# Power_Management.net
KiCad netlist of a schematic drawn in Altium Designer
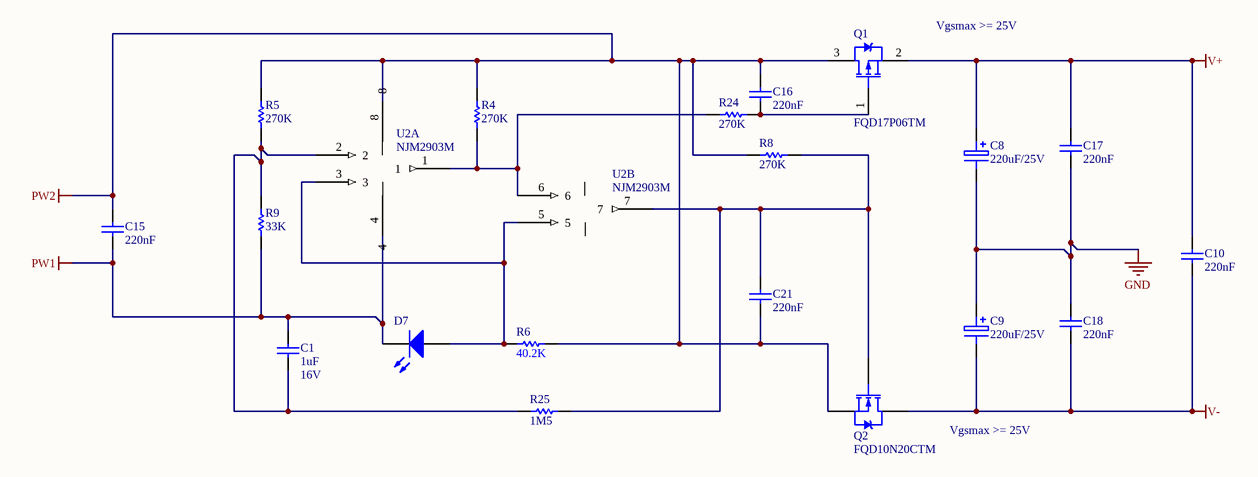
[diagram p0: Power Management.SchDoc]

(export (version "E")
  (design (tool "Eeschema 10.0.6"))
  (components
    (comp (ref "C1")
      (value "1uF")
      (footprint "CAPC1608L")
      (description "CAP CER 1uF Y5V -20% +80% 16V 0603")
      (fields (field (name "MAX VOLTAGE") "16V"))
      (libsource (lib "ECE Components_16_2") (part "CC_1uF_0603"))
    )
    (comp (ref "C8")
      (value "220uF/25V")
      (footprint "UUQ1E221MCL1GS")
      (description "220µF 25V Aluminum Capacitors Radial, Can - SMD 1000 Hrs @ 105°C")
      (fields (field (name "MANUFACTURER") "Nichcon"))
      (libsource (lib "ECE Components_16_2") (part "CA_100uF_16V"))
    )
    (comp (ref "C9")
      (value "220uF/25V")
      (footprint "UUQ1E221MCL1GS")
      (description "220µF 25V Aluminum Capacitors Radial, Can - SMD 1000 Hrs @ 105°C")
      (fields (field (name "MANUFACTURER") "Nichcon"))
      (libsource (lib "ECE Components_16_2") (part "CA_100uF_16V"))
    )
    (comp (ref "C10")
      (value "220nF")
      (footprint "CAPC1608L")
      (description "CAP CER 220nF Y5V -20% +80% 25V 0603")
      (libsource (lib "ECE Components_16_2") (part "CC_220nF_0603"))
    )
    (comp (ref "C15")
      (value "220nF")
      (footprint "CAPC1608L")
      (description "CAP CER 220nF Y5V -20% +80% 25V 0603")
      (libsource (lib "ECE Components_16_2") (part "CC_220nF_0603"))
    )
    (comp (ref "C16")
      (value "220nF")
      (footprint "CAPC1608L")
      (description "CAP CER 220nF Y5V -20% +80% 25V 0603")
      (libsource (lib "ECE Components_16_2") (part "CC_220nF_0603"))
    )
    (comp (ref "C17")
      (value "220nF")
      (footprint "CAPC1608L")
      (description "CAP CER 220nF Y5V -20% +80% 25V 0603")
      (libsource (lib "ECE Components_16_2") (part "CC_220nF_0603"))
    )
    (comp (ref "C18")
      (value "220nF")
      (footprint "CAPC1608L")
      (description "CAP CER 220nF Y5V -20% +80% 25V 0603")
      (libsource (lib "ECE Components_16_2") (part "CC_220nF_0603"))
    )
    (comp (ref "C21")
      (value "220nF")
      (footprint "CAPC1608L")
      (description "CAP CER 220nF Y5V -20% +80% 25V 0603")
      (libsource (lib "ECE Components_16_2") (part "CC_220nF_0603"))
    )
    (comp (ref "D7")
      (value "H-E RED")
      (footprint "MV5764.MP4B")
      (description "LED Blue 270mcd 0603 SMD")
      (fields
        (field (name "MANUFACTURER") "WURTH ELEKTRONIK")
        (field (name "MANUFACTURER PART NUMBER") "MV5764.MP4B")
      )
      (libsource (lib "ECE Components_16_2") (part "DL_150060BS75000"))
    )
    (comp (ref "Q1")
      (value "FQD17P06TM")
      (footprint "FQD17P06TM")
      (description "P-Channel 60V 12A (Tc) 2.5W (Ta), 44W (Tc) Surface Mount D-Pak")
      (fields (field (name "MANUFACTURER PART NUMBER") "FQD17P06TM"))
      (libsource (lib "ECE Components_16_2") (part "TM_SSM3J328R"))
    )
    (comp (ref "Q2")
      (value "FQD10N20CTM")
      (footprint "FQD10N20CTM")
      (description "N-Channel Power MOSFET")
      (fields (field (name "PUBLISHER") "Altium Limited"))
      (libsource (lib "Miscellaneous Devices") (part "NMOS-2"))
    )
    (comp (ref "R4")
      (value "270K")
      (footprint "RESC1608L")
      (description "RES 270K OHM 1/10W 5% 0603 SMD")
      (libsource (lib "ECE Components_16_2") (part "RS_270K"))
    )
    (comp (ref "R5")
      (value "270K")
      (footprint "RESC1608L")
      (description "RES 270K OHM 1/10W 5% 0603 SMD")
      (libsource (lib "ECE Components_16_2") (part "RS_270K"))
    )
    (comp (ref "R6")
      (value "40.2K")
      (footprint "RESC1608L")
      (description "RES 43K OHM 1/10W 5% 0603 SMD")
      (libsource (lib "ECE Components_16_2") (part "RS_43K"))
    )
    (comp (ref "R8")
      (value "270K")
      (footprint "RESC1608L")
      (description "RES 270K OHM 1/10W 5% 0603 SMD")
      (libsource (lib "ECE Components_16_2") (part "RS_270K"))
    )
    (comp (ref "R9")
      (value "33K")
      (footprint "RESC1608L")
      (description "RES 33.0K OHM 1/10W 5% 0603 SMD")
      (libsource (lib "ECE Components_16_2") (part "RS_33K"))
    )
    (comp (ref "R24")
      (value "270K")
      (footprint "RESC1608L")
      (description "RES 270K OHM 1/10W 5% 0603 SMD")
      (libsource (lib "ECE Components_16_2") (part "RS_270K"))
    )
    (comp (ref "R25")
      (value "1M5")
      (footprint "RESC1608L")
      (description "RES 1.5M OHM 1/10W 5% 0603 SMD")
      (libsource (lib "ECE Components_16_2") (part "RS_1M5"))
    )
    (comp (ref "U2") (value "NJM2903M") (footprint "NJM2903M") (libsource (lib "") (part "NJM2903D_1")))
  )
  (nets
    (net (code "1") (name "GND") (class "Default")
      (node (ref "C17") (pin "1") (pinfunction "1_1") (pintype "passive"))
      (node (ref "C18") (pin "2") (pinfunction "2_2") (pintype "passive"))
      (node (ref "C8") (pin "1") (pintype "passive"))
      (node (ref "C9") (pin "2") (pintype "passive"))
    )
    (net (code "2") (name "Net-(C1-Pad1)") (class "Default")
      (node (ref "C1") (pin "1") (pinfunction "1_1") (pintype "passive"))
      (node (ref "R25") (pin "1") (pinfunction "1_1") (pintype "passive"))
      (node (ref "R5") (pin "1") (pinfunction "1_1") (pintype "passive"))
      (node (ref "R9") (pin "2") (pinfunction "2_2") (pintype "passive"))
      (node (ref "U2") (pin "2") (pinfunction "2_2") (pintype "input"))
    )
    (net (code "3") (name "Net-(C16-Pad1)") (class "Default")
      (node (ref "C16") (pin "1") (pinfunction "1_1") (pintype "passive"))
      (node (ref "Q1") (pin "1") (pinfunction "1_1") (pintype "passive"))
      (node (ref "R24") (pin "2") (pinfunction "2_2") (pintype "passive"))
    )
    (net (code "4") (name "Net-(D7-A)") (class "Default")
      (node (ref "D7") (pin "2") (pinfunction "A_2") (pintype "passive"))
      (node (ref "R6") (pin "1") (pinfunction "1_1") (pintype "passive"))
      (node (ref "U2") (pin "3") (pinfunction "3_3") (pintype "input"))
      (node (ref "U2") (pin "5") (pinfunction "5_5") (pintype "input"))
    )
    (net (code "5") (name "Net-(Q2-G)") (class "Default")
      (node (ref "C21") (pin "2") (pinfunction "2_2") (pintype "passive"))
      (node (ref "Q2") (pin "1") (pinfunction "G_1") (pintype "passive"))
      (node (ref "R25") (pin "2") (pinfunction "2_2") (pintype "passive"))
      (node (ref "R8") (pin "2") (pinfunction "2_2") (pintype "passive"))
      (node (ref "U2") (pin "7") (pinfunction "7_7") (pintype "output"))
    )
    (net (code "6") (name "Net-(R24-Pad1)") (class "Default")
      (node (ref "R24") (pin "1") (pinfunction "1_1") (pintype "passive"))
      (node (ref "R4") (pin "1") (pinfunction "1_1") (pintype "passive"))
      (node (ref "U2") (pin "1") (pinfunction "1_1") (pintype "output"))
      (node (ref "U2") (pin "6") (pinfunction "6_6") (pintype "input"))
    )
    (net (code "7") (name "PW1") (class "Default")
      (node (ref "C1") (pin "2") (pinfunction "2_2") (pintype "passive"))
      (node (ref "C15") (pin "1") (pinfunction "1_1") (pintype "passive"))
      (node (ref "D7") (pin "1") (pinfunction "K_1") (pintype "passive"))
      (node (ref "R9") (pin "1") (pinfunction "1_1") (pintype "passive"))
    )
    (net (code "8") (name "PW2") (class "Default")
      (node (ref "C15") (pin "2") (pinfunction "2_2") (pintype "passive"))
      (node (ref "C16") (pin "2") (pinfunction "2_2") (pintype "passive"))
      (node (ref "C21") (pin "1") (pinfunction "1_1") (pintype "passive"))
      (node (ref "Q1") (pin "3") (pinfunction "3_3") (pintype "passive"))
      (node (ref "Q2") (pin "3") (pinfunction "S_3") (pintype "passive"))
      (node (ref "R4") (pin "2") (pinfunction "2_2") (pintype "passive"))
      (node (ref "R5") (pin "2") (pinfunction "2_2") (pintype "passive"))
      (node (ref "R6") (pin "2") (pinfunction "2_2") (pintype "passive"))
      (node (ref "R8") (pin "1") (pinfunction "1_1") (pintype "passive"))
    )
    (net (code "9") (name "V+") (class "Default")
      (node (ref "C10") (pin "2") (pinfunction "2_2") (pintype "passive"))
      (node (ref "C17") (pin "2") (pinfunction "2_2") (pintype "passive"))
      (node (ref "C8") (pin "2") (pintype "passive"))
      (node (ref "Q1") (pin "2") (pinfunction "2_2") (pintype "passive"))
    )
    (net (code "10") (name "V-") (class "Default")
      (node (ref "C10") (pin "1") (pinfunction "1_1") (pintype "passive"))
      (node (ref "C18") (pin "1") (pinfunction "1_1") (pintype "passive"))
      (node (ref "C9") (pin "1") (pintype "passive"))
      (node (ref "Q2") (pin "2") (pinfunction "D_2") (pintype "passive"))
    )
    (net (code "11") (name "unconnected-(U2-Pad4)") (class "Default")
      (node (ref "U2") (pin "4") (pinfunction "4_4") (pintype "passive"))
    )
    (net (code "12") (name "unconnected-(U2-Pad8)") (class "Default")
      (node (ref "U2") (pin "8") (pinfunction "8_8") (pintype "passive"))
    )
  )
)
